# Schematic_11_2017_-_3Layersv7_2.net
KiCad netlist of a schematic drawn in EAGLE
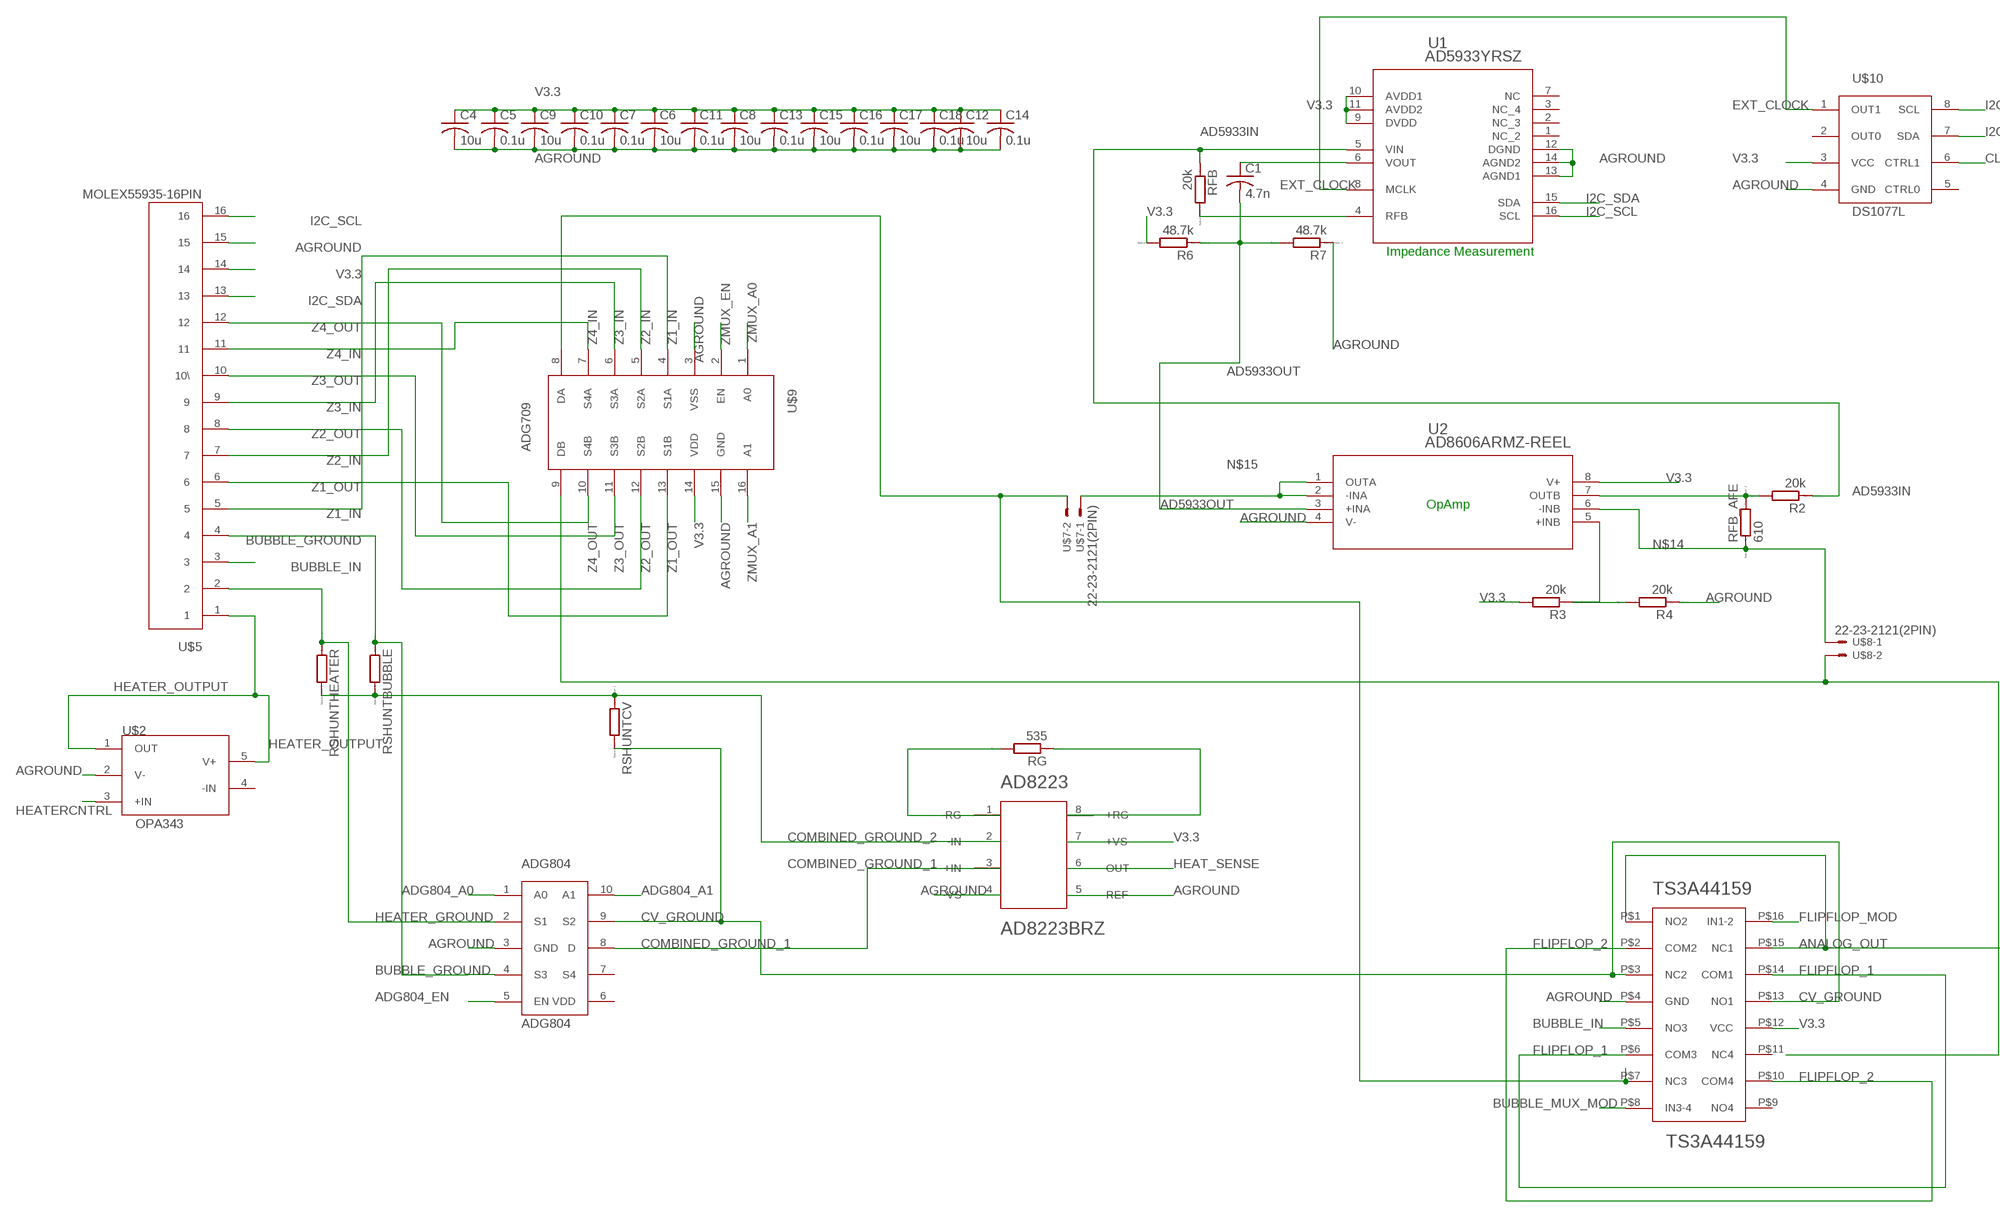
[diagram p0: schematic, sheet 1, part 1 of 2]
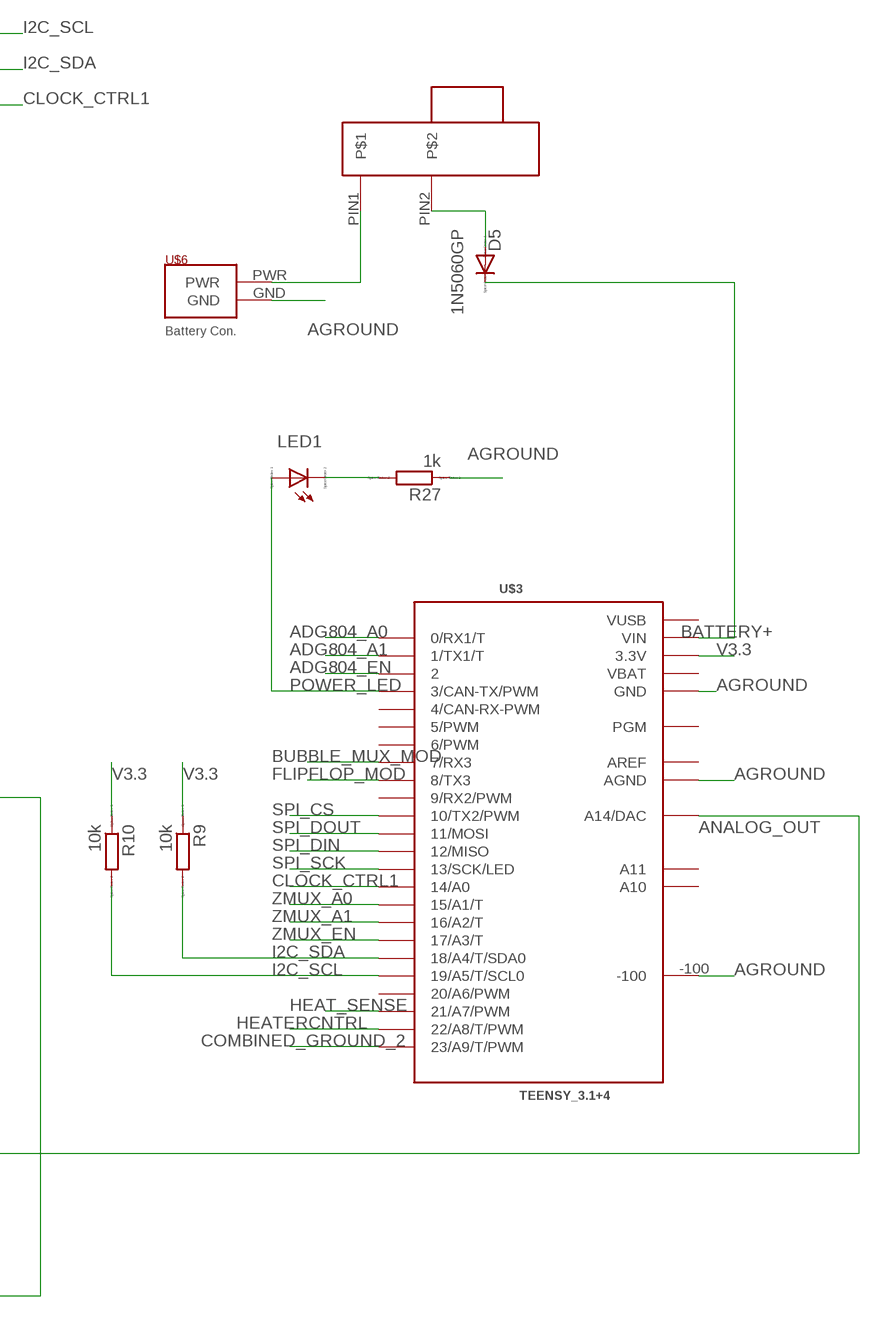
[diagram p1: schematic, sheet 1, part 2 of 2]

(export (version "E")
  (design (tool "Eeschema 10.0.6"))
  (components
    (comp (ref "ADG804")
      (value "ADG804")
      (footprint "eagle-import:MSOP10")
      (libsource (lib "eagle-import") (part "ADG804"))
    )
    (comp (ref "C1")
      (value "4.7n")
      (footprint "eagle-import:C1206")
      (libsource (lib "eagle-import") (part "C-USC1206"))
    )
    (comp (ref "C4")
      (value "10u")
      (footprint "eagle-import:C1206")
      (libsource (lib "eagle-import") (part "C-USC1206"))
    )
    (comp (ref "C5")
      (value "0.1u")
      (footprint "eagle-import:C1206")
      (libsource (lib "eagle-import") (part "C-USC1206"))
    )
    (comp (ref "C6")
      (value "10u")
      (footprint "eagle-import:C1206")
      (libsource (lib "eagle-import") (part "C-USC1206"))
    )
    (comp (ref "C7")
      (value "0.1u")
      (footprint "eagle-import:C1206")
      (libsource (lib "eagle-import") (part "C-USC1206"))
    )
    (comp (ref "C8")
      (value "10u")
      (footprint "eagle-import:C1206")
      (libsource (lib "eagle-import") (part "C-USC1206"))
    )
    (comp (ref "C9")
      (value "10u")
      (footprint "eagle-import:C1206")
      (libsource (lib "eagle-import") (part "C-USC1206"))
    )
    (comp (ref "C10")
      (value "0.1u")
      (footprint "eagle-import:C1206")
      (libsource (lib "eagle-import") (part "C-USC1206"))
    )
    (comp (ref "C11")
      (value "0.1u")
      (footprint "eagle-import:C1206")
      (libsource (lib "eagle-import") (part "C-USC1206"))
    )
    (comp (ref "C12")
      (value "10u")
      (footprint "eagle-import:C1206")
      (libsource (lib "eagle-import") (part "C-USC1206"))
    )
    (comp (ref "C13")
      (value "0.1u")
      (footprint "eagle-import:C1206")
      (libsource (lib "eagle-import") (part "C-USC1206"))
    )
    (comp (ref "C14")
      (value "0.1u")
      (footprint "eagle-import:C1206")
      (libsource (lib "eagle-import") (part "C-USC1206"))
    )
    (comp (ref "C15")
      (value "10u")
      (footprint "eagle-import:C1206")
      (libsource (lib "eagle-import") (part "C-USC1206"))
    )
    (comp (ref "C16")
      (value "0.1u")
      (footprint "eagle-import:C1206")
      (libsource (lib "eagle-import") (part "C-USC1206"))
    )
    (comp (ref "C17")
      (value "10u")
      (footprint "eagle-import:C1206")
      (libsource (lib "eagle-import") (part "C-USC1206"))
    )
    (comp (ref "C18")
      (value "0.1u")
      (footprint "eagle-import:C1206")
      (libsource (lib "eagle-import") (part "C-USC1206"))
    )
    (comp (ref "D5")
      (value "1N5060GP")
      (footprint "eagle-import:DO15-12")
      (libsource (lib "eagle-import") (part "1N5060GP"))
    )
    (comp (ref "LED1")
      (value "LED_ELD260")
      (footprint "eagle-import:LED_LD260")
      (libsource (lib "eagle-import") (part "LED_ELD260"))
    )
    (comp (ref "R2")
      (value "20k")
      (footprint "eagle-import:R1206")
      (libsource (lib "eagle-import") (part "RR1206"))
    )
    (comp (ref "R3")
      (value "20k")
      (footprint "eagle-import:R1206")
      (libsource (lib "eagle-import") (part "RR1206"))
    )
    (comp (ref "R4")
      (value "20k")
      (footprint "eagle-import:R1206")
      (libsource (lib "eagle-import") (part "RR1206"))
    )
    (comp (ref "R6")
      (value "48.7k")
      (footprint "eagle-import:R1206")
      (libsource (lib "eagle-import") (part "RR1206"))
    )
    (comp (ref "R7")
      (value "48.7k")
      (footprint "eagle-import:R1206")
      (libsource (lib "eagle-import") (part "RR1206"))
    )
    (comp (ref "R9")
      (value "10k")
      (footprint "eagle-import:R1206")
      (libsource (lib "eagle-import") (part "RR1206"))
    )
    (comp (ref "R10")
      (value "10k")
      (footprint "eagle-import:R1206")
      (libsource (lib "eagle-import") (part "RR1206"))
    )
    (comp (ref "R27")
      (value "1k")
      (footprint "eagle-import:R1206")
      (libsource (lib "eagle-import") (part "RR1206"))
    )
    (comp (ref "RFB")
      (value "20k")
      (footprint "eagle-import:R1206")
      (libsource (lib "eagle-import") (part "RR1206"))
    )
    (comp (ref "RFB_AFE")
      (value "610")
      (footprint "eagle-import:R1206")
      (libsource (lib "eagle-import") (part "RR1206"))
    )
    (comp (ref "RG")
      (value "535")
      (footprint "eagle-import:R1206")
      (libsource (lib "eagle-import") (part "eagle-ltspice_217_RR1206"))
    )
    (comp (ref "RSHUNTBUBBLE")
      (value "RR1206")
      (footprint "eagle-import:R1206")
      (libsource (lib "eagle-import") (part "eagle-ltspice_217_RR1206"))
    )
    (comp (ref "RSHUNTCV")
      (value "RR1206")
      (footprint "eagle-import:R1206")
      (libsource (lib "eagle-import") (part "eagle-ltspice_217_RR1206"))
    )
    (comp (ref "RSHUNTHEATER")
      (value "RR1206")
      (footprint "eagle-import:R1206")
      (libsource (lib "eagle-import") (part "eagle-ltspice_217_RR1206"))
    )
    (comp (ref "TS3A44159")
      (value "TS3A44159")
      (footprint "eagle-import:TSSOP16")
      (libsource (lib "eagle-import") (part "TS3A44159"))
    )
    (comp (ref "U$1")
      (value "AD8223BRZ")
      (footprint "eagle-import:R-8")
      (libsource (lib "eagle-import") (part "AD8223BRZ"))
    )
    (comp (ref "U$2")
      (value "OPA343")
      (footprint "eagle-import:SOT95P280X145-5N")
      (libsource (lib "eagle-import") (part "OPA343"))
    )
    (comp (ref "U$3")
      (value "TEENSY_3.1+4")
      (footprint "eagle-import:TEENSY_3.1+4")
      (libsource (lib "eagle-import") (part "TEENSY_3.1+4"))
    )
    (comp (ref "U$4")
      (value "C&KSWITCH")
      (footprint "eagle-import:2POS_SWITCH")
      (libsource (lib "eagle-import") (part "C&KSWITCH"))
    )
    (comp (ref "U$5")
      (value "MOLEX55935-16PIN")
      (footprint "eagle-import:MOLEX55935-16PIN")
      (libsource (lib "eagle-import") (part "MOLEX55935-16PIN"))
    )
    (comp (ref "U$6")
      (value "PH_2PIN")
      (footprint "eagle-import:JST_PH_2PIN")
      (libsource (lib "eagle-import") (part "PH_2PIN"))
    )
    (comp (ref "U$7")
      (value "22-23-2121(2PIN)")
      (footprint "eagle-import:22-23-2121(2PIN)")
      (libsource (lib "eagle-import") (part "22-23-2121(2PIN)"))
    )
    (comp (ref "U$8")
      (value "22-23-2121(2PIN)")
      (footprint "eagle-import:22-23-2121(2PIN)")
      (libsource (lib "eagle-import") (part "22-23-2121(2PIN)"))
    )
    (comp (ref "U$9")
      (value "ADG709")
      (footprint "eagle-import:TSSOP16")
      (libsource (lib "eagle-import") (part "ADG709"))
    )
    (comp (ref "U$10")
      (value "DS1077L")
      (footprint "eagle-import:SO08")
      (libsource (lib "eagle-import") (part "DS1077L"))
    )
    (comp (ref "U1")
      (value "AD5933YRSZ")
      (footprint "eagle-import:RS_16")
      (libsource (lib "eagle-import") (part "AD5933YRSZ"))
    )
    (comp (ref "U2")
      (value "AD8606ARMZ-REEL")
      (footprint "eagle-import:RM_8")
      (fields (field (name "MANUFACTURER_PART_NUMBER") "AD8606ARMZREEL"))
      (libsource (lib "eagle-import") (part "AD8606ARMZ-REEL"))
    )
  )
  (nets
    (net (code "1") (name "/AD5933IN") (class "Default")
      (node (ref "R2") (pin "1") (pinfunction "1_1") (pintype "passive"))
      (node (ref "RFB") (pin "1") (pinfunction "1_1") (pintype "passive"))
      (node (ref "U1") (pin "5") (pinfunction "VIN_5") (pintype "passive"))
    )
    (net (code "2") (name "/AD5933OUT") (class "Default")
      (node (ref "C1") (pin "2") (pinfunction "2_2") (pintype "passive"))
      (node (ref "R6") (pin "1") (pinfunction "1_1") (pintype "passive"))
      (node (ref "R7") (pin "2") (pinfunction "2_2") (pintype "passive"))
      (node (ref "U2") (pin "3") (pinfunction "+INA_3") (pintype "passive"))
    )
    (net (code "3") (name "/ADG804_A0") (class "Default")
      (node (ref "ADG804") (pin "1") (pinfunction "A0_1") (pintype "bidirectional"))
      (node (ref "U$3") (pin "0") (pinfunction "0/RX1/T_0") (pintype "bidirectional"))
    )
    (net (code "4") (name "/ADG804_A1") (class "Default")
      (node (ref "ADG804") (pin "10") (pinfunction "A1_10") (pintype "bidirectional"))
      (node (ref "U$3") (pin "1") (pinfunction "1/TX1/T_1") (pintype "bidirectional"))
    )
    (net (code "5") (name "/ADG804_EN") (class "Default")
      (node (ref "ADG804") (pin "5") (pinfunction "EN_5") (pintype "bidirectional"))
      (node (ref "U$3") (pin "2") (pinfunction "2_2") (pintype "bidirectional"))
    )
    (net (code "6") (name "/AGROUND") (class "Default")
      (node (ref "ADG804") (pin "3") (pinfunction "GND_3") (pintype "bidirectional"))
      (node (ref "C10") (pin "2") (pinfunction "2_2") (pintype "passive"))
      (node (ref "C11") (pin "2") (pinfunction "2_2") (pintype "passive"))
      (node (ref "C12") (pin "2") (pinfunction "2_2") (pintype "passive"))
      (node (ref "C13") (pin "2") (pinfunction "2_2") (pintype "passive"))
      (node (ref "C14") (pin "2") (pinfunction "2_2") (pintype "passive"))
      (node (ref "C15") (pin "2") (pinfunction "2_2") (pintype "passive"))
      (node (ref "C16") (pin "2") (pinfunction "2_2") (pintype "passive"))
      (node (ref "C17") (pin "2") (pinfunction "2_2") (pintype "passive"))
      (node (ref "C18") (pin "2") (pinfunction "2_2") (pintype "passive"))
      (node (ref "C4") (pin "2") (pinfunction "2_2") (pintype "passive"))
      (node (ref "C5") (pin "2") (pinfunction "2_2") (pintype "passive"))
      (node (ref "C6") (pin "2") (pinfunction "2_2") (pintype "passive"))
      (node (ref "C7") (pin "2") (pinfunction "2_2") (pintype "passive"))
      (node (ref "C8") (pin "2") (pinfunction "2_2") (pintype "passive"))
      (node (ref "C9") (pin "2") (pinfunction "2_2") (pintype "passive"))
      (node (ref "R27") (pin "1") (pinfunction "1_1") (pintype "passive"))
      (node (ref "R4") (pin "1") (pinfunction "1_1") (pintype "passive"))
      (node (ref "R7") (pin "1") (pinfunction "1_1") (pintype "passive"))
      (node (ref "TS3A44159") (pin "P$4") (pinfunction "GND_P$4") (pintype "bidirectional"))
      (node (ref "U$1") (pin "4") (pinfunction "-VS_4") (pintype "bidirectional"))
      (node (ref "U$1") (pin "5") (pinfunction "REF_5") (pintype "bidirectional"))
      (node (ref "U$10") (pin "4") (pinfunction "GND_4") (pintype "bidirectional"))
      (node (ref "U$2") (pin "2") (pinfunction "V-_2") (pintype "bidirectional"))
      (node (ref "U$3") (pin "-100") (pinfunction "-100_-100") (pintype "bidirectional"))
      (node (ref "U$3") (pin "AGND") (pinfunction "AGND_AGND") (pintype "power_in"))
      (node (ref "U$3") (pin "GND1") (pinfunction "GND_GND1") (pintype "power_in"))
      (node (ref "U$5") (pin "15") (pinfunction "15_15") (pintype "bidirectional"))
      (node (ref "U$6") (pin "GND") (pinfunction "GND_GND") (pintype "power_in"))
      (node (ref "U$9") (pin "15") (pinfunction "GND_15") (pintype "bidirectional"))
      (node (ref "U$9") (pin "3") (pinfunction "VSS_3") (pintype "bidirectional"))
      (node (ref "U1") (pin "12") (pinfunction "DGND_12") (pintype "passive"))
      (node (ref "U1") (pin "13") (pinfunction "AGND1_13") (pintype "passive"))
      (node (ref "U1") (pin "14") (pinfunction "AGND2_14") (pintype "passive"))
      (node (ref "U2") (pin "4") (pinfunction "V-_4") (pintype "power_in"))
    )
    (net (code "7") (name "/ANALOG_OUT") (class "Default")
      (node (ref "TS3A44159") (pin "P$1") (pinfunction "NO2_P$1") (pintype "bidirectional"))
      (node (ref "TS3A44159") (pin "P$15") (pinfunction "NC1_P$15") (pintype "bidirectional"))
      (node (ref "U$3") (pin "A14") (pinfunction "A14/DAC_A14") (pintype "bidirectional"))
    )
    (net (code "8") (name "/AREF") (class "Default")
      (node (ref "U$3") (pin "AREF") (pinfunction "AREF_AREF") (pintype "power_in"))
    )
    (net (code "9") (name "/BATTERY+") (class "Default")
      (node (ref "D5") (pin "C") (pinfunction "C_C") (pintype "passive"))
      (node (ref "U$3") (pin "VIN") (pinfunction "VIN_VIN") (pintype "power_in"))
    )
    (net (code "10") (name "/BUBBLE_GROUND") (class "Default")
      (node (ref "ADG804") (pin "4") (pinfunction "S3_4") (pintype "bidirectional"))
      (node (ref "RSHUNTBUBBLE") (pin "1") (pinfunction "1_1") (pintype "passive"))
      (node (ref "U$5") (pin "4") (pinfunction "4_4") (pintype "bidirectional"))
    )
    (net (code "11") (name "/BUBBLE_IN") (class "Default")
      (node (ref "TS3A44159") (pin "P$5") (pinfunction "NO3_P$5") (pintype "bidirectional"))
      (node (ref "U$5") (pin "3") (pinfunction "3_3") (pintype "bidirectional"))
    )
    (net (code "12") (name "/BUBBLE_MUX_MOD") (class "Default")
      (node (ref "TS3A44159") (pin "P$8") (pinfunction "IN3-4_P$8") (pintype "bidirectional"))
      (node (ref "U$3") (pin "7") (pinfunction "7/RX3_7") (pintype "bidirectional"))
    )
    (net (code "13") (name "/CLOCK_CTRL1") (class "Default")
      (node (ref "U$10") (pin "6") (pinfunction "CTRL1_6") (pintype "bidirectional"))
      (node (ref "U$3") (pin "14/A0") (pinfunction "14/A0_14/A0") (pintype "bidirectional"))
    )
    (net (code "14") (name "/COMBINED_GROUND_1") (class "Default")
      (node (ref "ADG804") (pin "8") (pinfunction "D_8") (pintype "bidirectional"))
      (node (ref "U$1") (pin "3") (pinfunction "+IN_3") (pintype "bidirectional"))
    )
    (net (code "15") (name "/COMBINED_GROUND_2") (class "Default")
      (node (ref "RSHUNTBUBBLE") (pin "2") (pinfunction "2_2") (pintype "passive"))
      (node (ref "RSHUNTCV") (pin "1") (pinfunction "1_1") (pintype "passive"))
      (node (ref "RSHUNTHEATER") (pin "2") (pinfunction "2_2") (pintype "passive"))
      (node (ref "U$1") (pin "2") (pinfunction "-IN_2") (pintype "bidirectional"))
      (node (ref "U$3") (pin "23/A9") (pinfunction "23/A9/T/PWM_23/A9") (pintype "bidirectional"))
    )
    (net (code "16") (name "/CV_GROUND") (class "Default")
      (node (ref "ADG804") (pin "9") (pinfunction "S2_9") (pintype "bidirectional"))
      (node (ref "RSHUNTCV") (pin "2") (pinfunction "2_2") (pintype "passive"))
      (node (ref "TS3A44159") (pin "P$13") (pinfunction "NO1_P$13") (pintype "bidirectional"))
      (node (ref "TS3A44159") (pin "P$3") (pinfunction "NC2_P$3") (pintype "bidirectional"))
    )
    (net (code "17") (name "/EXT_CLOCK") (class "Default")
      (node (ref "U$10") (pin "1") (pinfunction "OUT1_1") (pintype "bidirectional"))
      (node (ref "U1") (pin "8") (pinfunction "MCLK_8") (pintype "passive"))
    )
    (net (code "18") (name "/FLIPFLOP_1") (class "Default")
      (node (ref "TS3A44159") (pin "P$14") (pinfunction "COM1_P$14") (pintype "bidirectional"))
      (node (ref "TS3A44159") (pin "P$6") (pinfunction "COM3_P$6") (pintype "bidirectional"))
    )
    (net (code "19") (name "/FLIPFLOP_2") (class "Default")
      (node (ref "TS3A44159") (pin "P$10") (pinfunction "COM4_P$10") (pintype "bidirectional"))
      (node (ref "TS3A44159") (pin "P$2") (pinfunction "COM2_P$2") (pintype "bidirectional"))
    )
    (net (code "20") (name "/FLIPFLOP_MOD") (class "Default")
      (node (ref "TS3A44159") (pin "P$16") (pinfunction "IN1-2_P$16") (pintype "bidirectional"))
      (node (ref "U$3") (pin "8") (pinfunction "8/TX3_8") (pintype "bidirectional"))
    )
    (net (code "21") (name "/HEATERCNTRL") (class "Default")
      (node (ref "U$2") (pin "3") (pinfunction "+IN_3") (pintype "bidirectional"))
      (node (ref "U$3") (pin "22/A8") (pinfunction "22/A8/T/PWM_22/A8") (pintype "bidirectional"))
    )
    (net (code "22") (name "/HEATER_GROUND") (class "Default")
      (node (ref "ADG804") (pin "2") (pinfunction "S1_2") (pintype "bidirectional"))
      (node (ref "RSHUNTHEATER") (pin "1") (pinfunction "1_1") (pintype "passive"))
      (node (ref "U$5") (pin "2") (pinfunction "2_2") (pintype "bidirectional"))
    )
    (net (code "23") (name "/HEATER_OUTPUT") (class "Default")
      (node (ref "U$2") (pin "1") (pinfunction "OUT_1") (pintype "bidirectional"))
      (node (ref "U$2") (pin "5") (pinfunction "V+_5") (pintype "bidirectional"))
      (node (ref "U$5") (pin "1") (pinfunction "1_1") (pintype "bidirectional"))
    )
    (net (code "24") (name "/HEAT_SENSE") (class "Default")
      (node (ref "U$1") (pin "6") (pinfunction "OUT_6") (pintype "bidirectional"))
      (node (ref "U$3") (pin "21/A7") (pinfunction "21/A7/PWM_21/A7") (pintype "bidirectional"))
    )
    (net (code "25") (name "/I2C_SCL") (class "Default")
      (node (ref "R10") (pin "2") (pinfunction "2_2") (pintype "passive"))
      (node (ref "U$10") (pin "8") (pinfunction "SCL_8") (pintype "bidirectional"))
      (node (ref "U$3") (pin "19/A5") (pinfunction "19/A5/T/SCL0_19/A5") (pintype "bidirectional"))
      (node (ref "U$5") (pin "16") (pinfunction "16_16") (pintype "bidirectional"))
      (node (ref "U1") (pin "16") (pinfunction "SCL_16") (pintype "passive"))
    )
    (net (code "26") (name "/I2C_SDA") (class "Default")
      (node (ref "R9") (pin "2") (pinfunction "2_2") (pintype "passive"))
      (node (ref "U$10") (pin "7") (pinfunction "SDA_7") (pintype "bidirectional"))
      (node (ref "U$3") (pin "18/A4") (pinfunction "18/A4/T/SDA0_18/A4") (pintype "bidirectional"))
      (node (ref "U$5") (pin "13") (pinfunction "13_13") (pintype "bidirectional"))
      (node (ref "U1") (pin "15") (pinfunction "SDA_15") (pintype "passive"))
    )
    (net (code "27") (name "/N$14") (class "Default")
      (node (ref "RFB_AFE") (pin "1") (pinfunction "1_1") (pintype "passive"))
      (node (ref "U$8") (pin "1") (pinfunction "S_1") (pintype "passive"))
      (node (ref "U2") (pin "6") (pinfunction "-INB_6") (pintype "passive"))
    )
    (net (code "28") (name "/N$15") (class "Default")
      (node (ref "U$7") (pin "1") (pinfunction "S_1") (pintype "passive"))
      (node (ref "U2") (pin "1") (pinfunction "OUTA_1") (pintype "passive"))
      (node (ref "U2") (pin "2") (pinfunction "-INA_2") (pintype "passive"))
    )
    (net (code "29") (name "/POWER_LED") (class "Default")
      (node (ref "LED1") (pin "A") (pinfunction "A_A") (pintype "passive"))
      (node (ref "U$3") (pin "3") (pinfunction "3/CAN-TX/PWM_3") (pintype "bidirectional"))
    )
    (net (code "30") (name "/SPI_CS") (class "Default")
      (node (ref "U$3") (pin "10") (pinfunction "10/TX2/PWM_10") (pintype "bidirectional"))
    )
    (net (code "31") (name "/SPI_DIN") (class "Default")
      (node (ref "U$3") (pin "12") (pinfunction "12/MISO_12") (pintype "bidirectional"))
    )
    (net (code "32") (name "/SPI_DOUT") (class "Default")
      (node (ref "U$3") (pin "11") (pinfunction "11/MOSI_11") (pintype "bidirectional"))
    )
    (net (code "33") (name "/SPI_SCK") (class "Default")
      (node (ref "U$3") (pin "13") (pinfunction "13/SCK/LED_13") (pintype "bidirectional"))
    )
    (net (code "34") (name "/V3.3") (class "Default")
      (node (ref "C10") (pin "1") (pinfunction "1_1") (pintype "passive"))
      (node (ref "C11") (pin "1") (pinfunction "1_1") (pintype "passive"))
      (node (ref "C12") (pin "1") (pinfunction "1_1") (pintype "passive"))
      (node (ref "C13") (pin "1") (pinfunction "1_1") (pintype "passive"))
      (node (ref "C14") (pin "1") (pinfunction "1_1") (pintype "passive"))
      (node (ref "C15") (pin "1") (pinfunction "1_1") (pintype "passive"))
      (node (ref "C16") (pin "1") (pinfunction "1_1") (pintype "passive"))
      (node (ref "C17") (pin "1") (pinfunction "1_1") (pintype "passive"))
      (node (ref "C18") (pin "1") (pinfunction "1_1") (pintype "passive"))
      (node (ref "C4") (pin "1") (pinfunction "1_1") (pintype "passive"))
      (node (ref "C5") (pin "1") (pinfunction "1_1") (pintype "passive"))
      (node (ref "C6") (pin "1") (pinfunction "1_1") (pintype "passive"))
      (node (ref "C7") (pin "1") (pinfunction "1_1") (pintype "passive"))
      (node (ref "C8") (pin "1") (pinfunction "1_1") (pintype "passive"))
      (node (ref "C9") (pin "1") (pinfunction "1_1") (pintype "passive"))
      (node (ref "R10") (pin "1") (pinfunction "1_1") (pintype "passive"))
      (node (ref "R3") (pin "2") (pinfunction "2_2") (pintype "passive"))
      (node (ref "R6") (pin "2") (pinfunction "2_2") (pintype "passive"))
      (node (ref "R9") (pin "1") (pinfunction "1_1") (pintype "passive"))
      (node (ref "TS3A44159") (pin "P$12") (pinfunction "VCC_P$12") (pintype "bidirectional"))
      (node (ref "U$1") (pin "7") (pinfunction "+VS_7") (pintype "bidirectional"))
      (node (ref "U$10") (pin "3") (pinfunction "VCC_3") (pintype "bidirectional"))
      (node (ref "U$3") (pin "3.3V") (pinfunction "3.3V_3.3V") (pintype "power_in"))
      (node (ref "U$3") (pin "3.3V1") (pinfunction "3.3V_3.3V1") (pintype "power_in"))
      (node (ref "U$5") (pin "14") (pinfunction "14_14") (pintype "bidirectional"))
      (node (ref "U$9") (pin "14") (pinfunction "VDD_14") (pintype "bidirectional"))
      (node (ref "U1") (pin "10") (pinfunction "AVDD1_10") (pintype "passive"))
      (node (ref "U1") (pin "11") (pinfunction "AVDD2_11") (pintype "passive"))
      (node (ref "U1") (pin "9") (pinfunction "DVDD_9") (pintype "passive"))
      (node (ref "U2") (pin "8") (pinfunction "V+_8") (pintype "power_in"))
    )
    (net (code "35") (name "/VBAT") (class "Default")
      (node (ref "U$3") (pin "VBAT") (pinfunction "VBAT_VBAT") (pintype "power_in"))
    )
    (net (code "36") (name "/VUSB") (class "Default")
      (node (ref "U$3") (pin "VUSB") (pinfunction "VUSB_VUSB") (pintype "power_in"))
    )
    (net (code "37") (name "/Z1_IN") (class "Default")
      (node (ref "U$5") (pin "5") (pinfunction "5_5") (pintype "bidirectional"))
      (node (ref "U$9") (pin "4") (pinfunction "S1A_4") (pintype "bidirectional"))
    )
    (net (code "38") (name "/Z1_OUT") (class "Default")
      (node (ref "U$5") (pin "6") (pinfunction "6_6") (pintype "bidirectional"))
      (node (ref "U$9") (pin "13") (pinfunction "S1B_13") (pintype "bidirectional"))
    )
    (net (code "39") (name "/Z2_IN") (class "Default")
      (node (ref "U$5") (pin "7") (pinfunction "7_7") (pintype "bidirectional"))
      (node (ref "U$9") (pin "5") (pinfunction "S2A_5") (pintype "bidirectional"))
    )
    (net (code "40") (name "/Z2_OUT") (class "Default")
      (node (ref "U$5") (pin "8") (pinfunction "8_8") (pintype "bidirectional"))
      (node (ref "U$9") (pin "12") (pinfunction "S2B_12") (pintype "bidirectional"))
    )
    (net (code "41") (name "/Z3_IN") (class "Default")
      (node (ref "U$5") (pin "9") (pinfunction "9_9") (pintype "bidirectional"))
      (node (ref "U$9") (pin "6") (pinfunction "S3A_6") (pintype "bidirectional"))
    )
    (net (code "42") (name "/Z3_OUT") (class "Default")
      (node (ref "U$5") (pin "10") (pinfunction "10\\_10") (pintype "bidirectional"))
      (node (ref "U$9") (pin "11") (pinfunction "S3B_11") (pintype "bidirectional"))
    )
    (net (code "43") (name "/Z4_IN") (class "Default")
      (node (ref "U$5") (pin "11") (pinfunction "11_11") (pintype "bidirectional"))
      (node (ref "U$9") (pin "7") (pinfunction "S4A_7") (pintype "bidirectional"))
    )
    (net (code "44") (name "/Z4_OUT") (class "Default")
      (node (ref "U$5") (pin "12") (pinfunction "12_12") (pintype "bidirectional"))
      (node (ref "U$9") (pin "10") (pinfunction "S4B_10") (pintype "bidirectional"))
    )
    (net (code "45") (name "/ZMUX_A0") (class "Default")
      (node (ref "U$3") (pin "15/A1") (pinfunction "15/A1/T_15/A1") (pintype "bidirectional"))
      (node (ref "U$9") (pin "1") (pinfunction "A0_1") (pintype "bidirectional"))
    )
    (net (code "46") (name "/ZMUX_A1") (class "Default")
      (node (ref "U$3") (pin "16/A2") (pinfunction "16/A2/T_16/A2") (pintype "bidirectional"))
      (node (ref "U$9") (pin "16") (pinfunction "A1_16") (pintype "bidirectional"))
    )
    (net (code "47") (name "/ZMUX_EN") (class "Default")
      (node (ref "U$3") (pin "17/A3") (pinfunction "17/A3/T_17/A3") (pintype "bidirectional"))
      (node (ref "U$9") (pin "2") (pinfunction "EN_2") (pintype "bidirectional"))
    )
    (net (code "48") (name "Net-(LED1-C)") (class "Default")
      (node (ref "LED1") (pin "K") (pinfunction "C_K") (pintype "passive"))
      (node (ref "R27") (pin "2") (pinfunction "2_2") (pintype "passive"))
    )
    (net (code "49") (name "Net-(TS3A44159-NC3)") (class "Default")
      (node (ref "TS3A44159") (pin "P$7") (pinfunction "NC3_P$7") (pintype "bidirectional"))
      (node (ref "U$7") (pin "2") (pinfunction "S_2") (pintype "passive"))
      (node (ref "U$9") (pin "8") (pinfunction "DA_8") (pintype "bidirectional"))
    )
    (net (code "50") (name "Net-(U$1-+RG)") (class "Default")
      (node (ref "RG") (pin "1") (pinfunction "1_1") (pintype "passive"))
      (node (ref "U$1") (pin "8") (pinfunction "+RG_8") (pintype "bidirectional"))
    )
    (net (code "51") (name "Net-(U$1--RG)") (class "Default")
      (node (ref "RG") (pin "2") (pinfunction "2_2") (pintype "passive"))
      (node (ref "U$1") (pin "1") (pinfunction "-RG_1") (pintype "bidirectional"))
    )
    (net (code "52") (name "Net-(U$4-P$1)") (class "Default")
      (node (ref "U$4") (pin "PIN1") (pinfunction "P$1_PIN1") (pintype "bidirectional"))
      (node (ref "U$6") (pin "PWR") (pinfunction "PWR_PWR") (pintype "power_in"))
    )
    (net (code "53") (name "Net-(U$4-P$2)") (class "Default")
      (node (ref "D5") (pin "A") (pinfunction "A_A") (pintype "passive"))
      (node (ref "U$4") (pin "PIN2") (pinfunction "P$2_PIN2") (pintype "bidirectional"))
    )
    (net (code "54") (name "Net-(U$8B-S)") (class "Default")
      (node (ref "U$8") (pin "2") (pinfunction "S_2") (pintype "passive"))
      (node (ref "U$9") (pin "9") (pinfunction "DB_9") (pintype "bidirectional"))
    )
    (net (code "55") (name "Net-(U1-RFB)") (class "Default")
      (node (ref "RFB") (pin "2") (pinfunction "2_2") (pintype "passive"))
      (node (ref "U1") (pin "4") (pinfunction "RFB_4") (pintype "passive"))
    )
    (net (code "56") (name "Net-(U1-VOUT)") (class "Default")
      (node (ref "C1") (pin "1") (pinfunction "1_1") (pintype "passive"))
      (node (ref "U1") (pin "6") (pinfunction "VOUT_6") (pintype "passive"))
    )
    (net (code "57") (name "Net-(U2-+INB)") (class "Default")
      (node (ref "R3") (pin "1") (pinfunction "1_1") (pintype "passive"))
      (node (ref "R4") (pin "2") (pinfunction "2_2") (pintype "passive"))
      (node (ref "U2") (pin "5") (pinfunction "+INB_5") (pintype "passive"))
    )
    (net (code "58") (name "Net-(U2-OUTB)") (class "Default")
      (node (ref "R2") (pin "2") (pinfunction "2_2") (pintype "passive"))
      (node (ref "RFB_AFE") (pin "2") (pinfunction "2_2") (pintype "passive"))
      (node (ref "U2") (pin "7") (pinfunction "OUTB_7") (pintype "passive"))
    )
    (net (code "59") (name "unconnected-(ADG804-S4-Pad7)") (class "Default")
      (node (ref "ADG804") (pin "7") (pinfunction "S4_7") (pintype "bidirectional"))
    )
    (net (code "60") (name "unconnected-(ADG804-VDD-Pad6)") (class "Default")
      (node (ref "ADG804") (pin "6") (pinfunction "VDD_6") (pintype "bidirectional"))
    )
    (net (code "61") (name "unconnected-(TS3A44159-NC4-PadP$11)") (class "Default")
      (node (ref "TS3A44159") (pin "P$11") (pinfunction "NC4_P$11") (pintype "bidirectional"))
    )
    (net (code "62") (name "unconnected-(TS3A44159-NO4-PadP$9)") (class "Default")
      (node (ref "TS3A44159") (pin "P$9") (pinfunction "NO4_P$9") (pintype "bidirectional"))
    )
    (net (code "63") (name "unconnected-(U$2--IN-Pad4)") (class "Default")
      (node (ref "U$2") (pin "4") (pinfunction "-IN_4") (pintype "bidirectional"))
    )
    (net (code "64") (name "unconnected-(U$3-4{slash}CAN-RX-PWM-Pad4)") (class "Default")
      (node (ref "U$3") (pin "4") (pinfunction "4/CAN-RX-PWM_4") (pintype "bidirectional"))
    )
    (net (code "65") (name "unconnected-(U$3-5{slash}PWM-Pad5)") (class "Default")
      (node (ref "U$3") (pin "5") (pinfunction "5/PWM_5") (pintype "bidirectional"))
    )
    (net (code "66") (name "unconnected-(U$3-6{slash}PWM-Pad6)") (class "Default")
      (node (ref "U$3") (pin "6") (pinfunction "6/PWM_6") (pintype "bidirectional"))
    )
    (net (code "67") (name "unconnected-(U$3-9{slash}RX2{slash}PWM-Pad9)") (class "Default")
      (node (ref "U$3") (pin "9") (pinfunction "9/RX2/PWM_9") (pintype "bidirectional"))
    )
    (net (code "68") (name "unconnected-(U$3-20{slash}A6{slash}PWM-Pad20{slash}A6)") (class "Default")
      (node (ref "U$3") (pin "20/A6") (pinfunction "20/A6/PWM_20/A6") (pintype "bidirectional"))
    )
    (net (code "69") (name "unconnected-(U$3-PadA10)") (class "Default")
      (node (ref "U$3") (pin "A10") (pinfunction "A10_A10") (pintype "bidirectional"))
    )
    (net (code "70") (name "unconnected-(U$3-PadA11)") (class "Default")
      (node (ref "U$3") (pin "A11") (pinfunction "A11_A11") (pintype "bidirectional"))
    )
    (net (code "71") (name "unconnected-(U$3-PadPGM)") (class "Default")
      (node (ref "U$3") (pin "PGM") (pinfunction "PGM_PGM") (pintype "bidirectional"))
    )
    (net (code "72") (name "unconnected-(U$10-CTRL0-Pad5)") (class "Default")
      (node (ref "U$10") (pin "5") (pinfunction "CTRL0_5") (pintype "bidirectional"))
    )
    (net (code "73") (name "unconnected-(U$10-OUT0-Pad2)") (class "Default")
      (node (ref "U$10") (pin "2") (pinfunction "OUT0_2") (pintype "bidirectional"))
    )
    (net (code "74") (name "unconnected-(U1-NC-Pad7)") (class "Default")
      (node (ref "U1") (pin "7") (pinfunction "NC_7") (pintype "passive"))
    )
    (net (code "75") (name "unconnected-(U1-NC_2-Pad1)") (class "Default")
      (node (ref "U1") (pin "1") (pinfunction "NC_2_1") (pintype "passive"))
    )
    (net (code "76") (name "unconnected-(U1-NC_3-Pad2)") (class "Default")
      (node (ref "U1") (pin "2") (pinfunction "NC_3_2") (pintype "passive"))
    )
    (net (code "77") (name "unconnected-(U1-NC_4-Pad3)") (class "Default")
      (node (ref "U1") (pin "3") (pinfunction "NC_4_3") (pintype "passive"))
    )
  )
)
